# psg-dual-electronic-switching.net
KiCad netlist of a schematic drawn in EAGLE
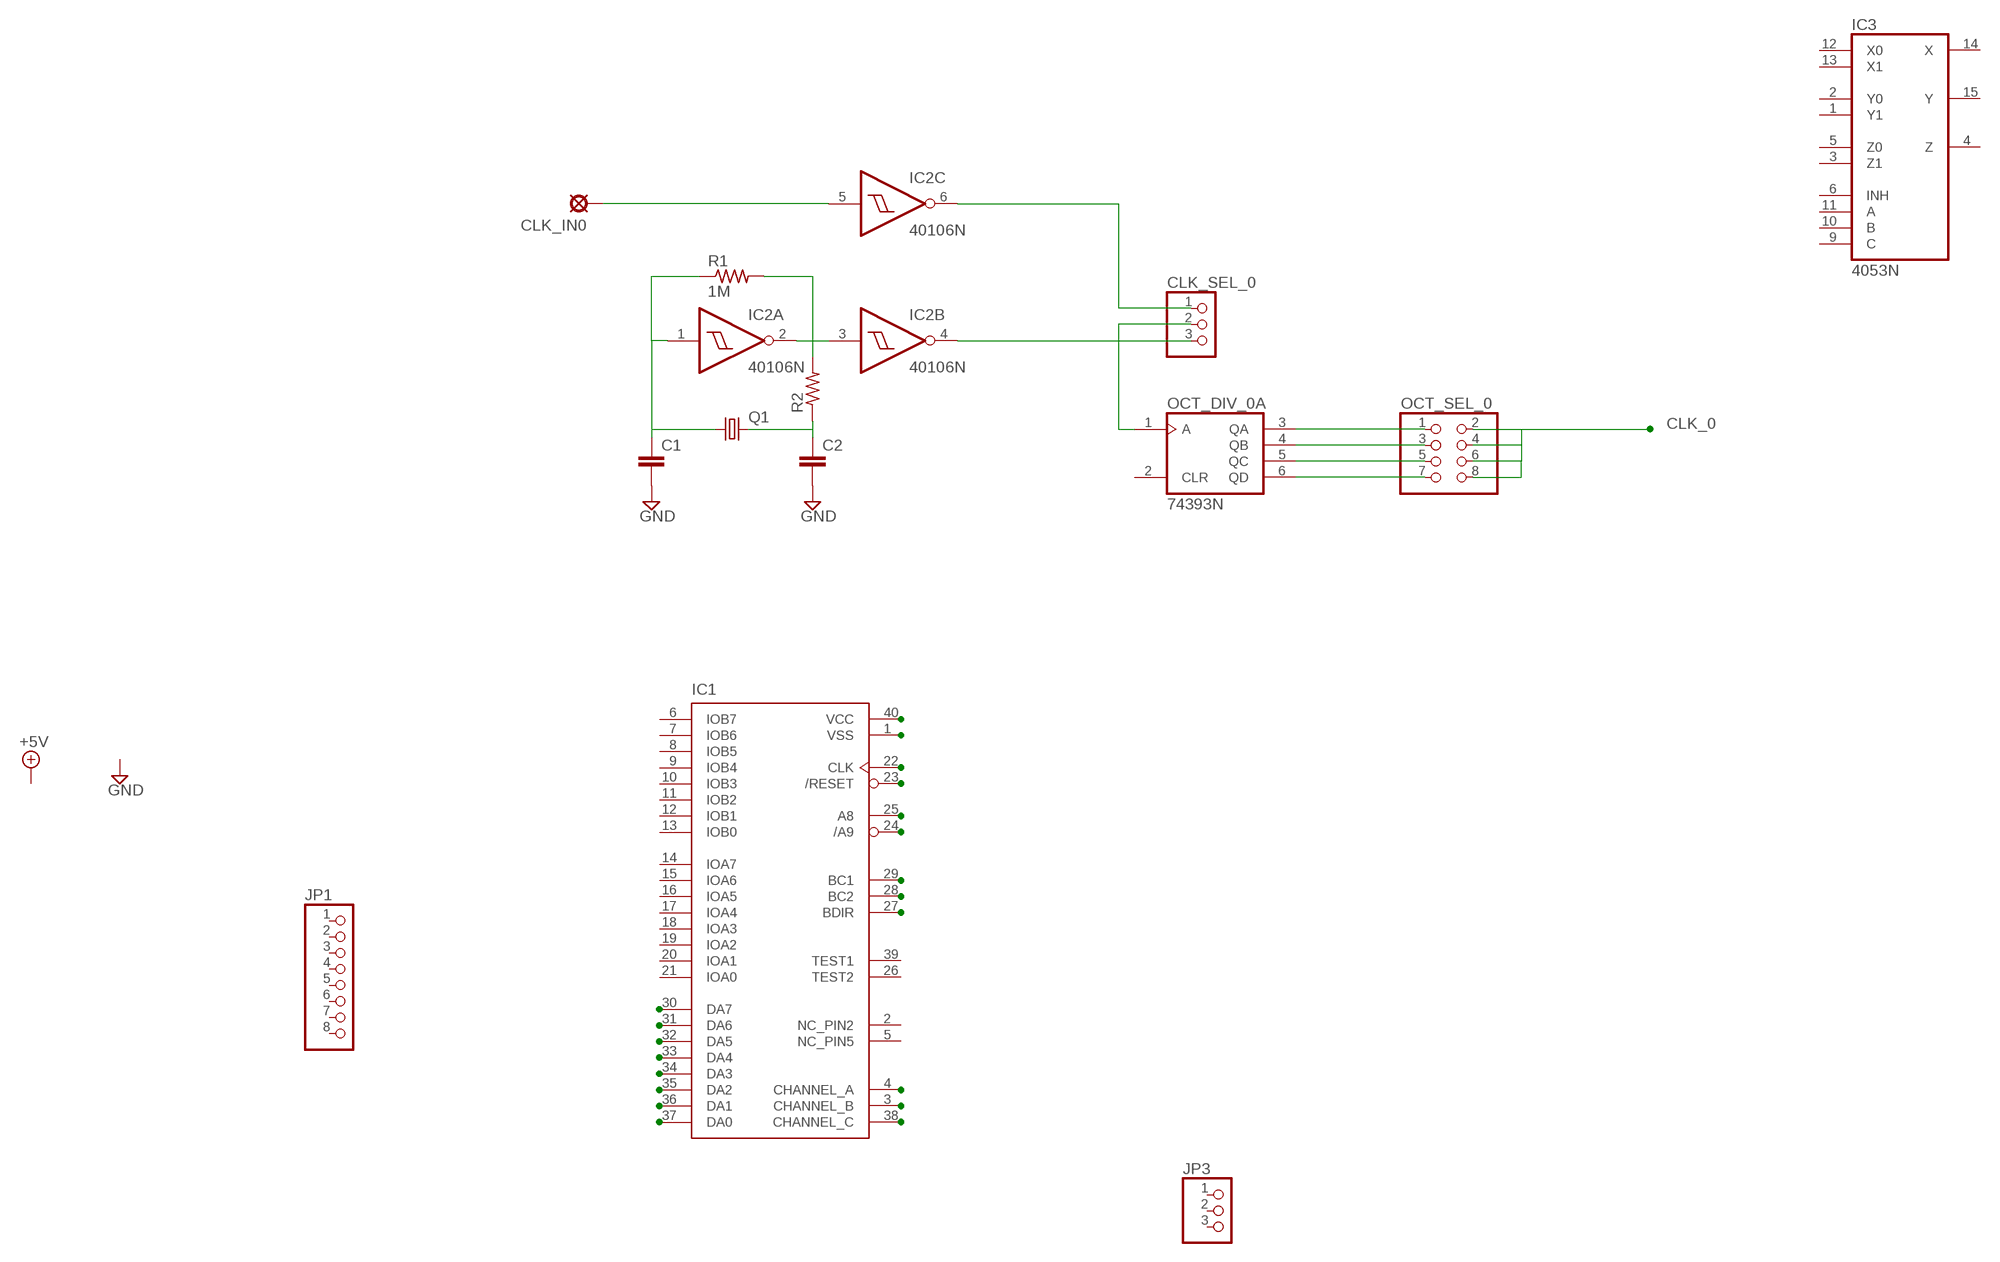
[diagram p0: schematic, sheet 1]

(export (version "E")
  (design (tool "Eeschema 10.0.6"))
  (components
    (comp (ref "C1")
      (value "050X030_0252")
      (footprint "eagle-import:050X030_025_2")
      (libsource (lib "eagle-import") (part "050X030_0252"))
    )
    (comp (ref "C2")
      (value "050X030_0252")
      (footprint "eagle-import:050X030_025_2")
      (libsource (lib "eagle-import") (part "050X030_0252"))
    )
    (comp (ref "CLK_IN0")
      (value "PAD")
      (footprint "eagle-import:SQUARE")
      (libsource (lib "eagle-import") (part "PAD"))
    )
    (comp (ref "CLK_SEL_0")
      (value "PINHD-1X3")
      (footprint "eagle-import:1X03")
      (libsource (lib "eagle-import") (part "PINHD-1X3"))
    )
    (comp (ref "IC1")
      (value "AY-3-8910")
      (footprint "eagle-import:DIL40")
      (libsource (lib "eagle-import") (part "AY-3-8910"))
    )
    (comp (ref "IC2")
      (value "40106N")
      (footprint "eagle-import:DIL14")
      (libsource (lib "eagle-import") (part "40106N"))
    )
    (comp (ref "IC3")
      (value "4053N")
      (footprint "eagle-import:DIL16")
      (libsource (lib "eagle-import") (part "4053N"))
    )
    (comp (ref "JP1")
      (value "PINHD-1X8")
      (footprint "eagle-import:1X08")
      (libsource (lib "eagle-import") (part "PINHD-1X8"))
    )
    (comp (ref "JP3")
      (value "PINHD-1X3")
      (footprint "eagle-import:1X03")
      (libsource (lib "eagle-import") (part "PINHD-1X3"))
    )
    (comp (ref "OCT_DIV_0")
      (value "74393N")
      (footprint "eagle-import:DIL14")
      (libsource (lib "eagle-import") (part "74393N"))
    )
    (comp (ref "OCT_SEL_0")
      (value "PINHD-2X4")
      (footprint "eagle-import:2X04")
      (libsource (lib "eagle-import") (part "PINHD-2X4"))
    )
    (comp (ref "Q1")
      (value "CRYSTALHC18U-V")
      (footprint "eagle-import:HC18U-V")
      (libsource (lib "eagle-import") (part "CRYSTALHC18U-V"))
    )
    (comp (ref "R1")
      (value "1M")
      (footprint "eagle-import:R0207_3")
      (libsource (lib "eagle-import") (part "6MM.3"))
    )
    (comp (ref "R2")
      (value "6MM.3")
      (footprint "eagle-import:R0207_3")
      (libsource (lib "eagle-import") (part "6MM.3"))
    )
  )
  (nets
    (net (code "2") (name "/CLK_0") (class "Default")
      (node (ref "OCT_SEL_0") (pin "2") (pinfunction "2_2") (pintype "passive"))
      (node (ref "OCT_SEL_0") (pin "4") (pinfunction "4_4") (pintype "passive"))
      (node (ref "OCT_SEL_0") (pin "6") (pinfunction "6_6") (pintype "passive"))
      (node (ref "OCT_SEL_0") (pin "8") (pinfunction "8_8") (pintype "passive"))
    )
    (net (code "3") (name "/VCC") (class "Default")
      (node (ref "IC1") (pin "40") (pinfunction "VCC_40") (pintype "power_in"))
    )
    (net (code "4") (name "/VSS") (class "Default")
      (node (ref "IC1") (pin "1") (pinfunction "VSS_1") (pintype "power_in"))
    )
    (net (code "5") (name "GND") (class "Default")
      (node (ref "C1") (pin "2") (pinfunction "2_2") (pintype "passive"))
      (node (ref "C2") (pin "2") (pinfunction "2_2") (pintype "passive"))
    )
    (net (code "6") (name "Net-(C2-Pad1)") (class "Default")
      (node (ref "C2") (pin "1") (pinfunction "1_1") (pintype "passive"))
      (node (ref "Q1") (pin "2") (pinfunction "2_2") (pintype "passive"))
      (node (ref "R2") (pin "1") (pinfunction "1_1") (pintype "passive"))
    )
    (net (code "7") (name "Net-(CLK_IN0-PAD)") (class "Default")
      (node (ref "CLK_IN0") (pin "1") (pinfunction "PAD_1") (pintype "passive"))
      (node (ref "IC2") (pin "5") (pinfunction "I_5") (pintype "input"))
    )
    (net (code "8") (name "Net-(IC2A-I)") (class "Default")
      (node (ref "C1") (pin "1") (pinfunction "1_1") (pintype "passive"))
      (node (ref "IC2") (pin "1") (pinfunction "I_1") (pintype "input"))
      (node (ref "Q1") (pin "1") (pinfunction "1_1") (pintype "passive"))
      (node (ref "R1") (pin "1") (pinfunction "1_1") (pintype "passive"))
    )
    (net (code "9") (name "Net-(IC2A-O)") (class "Default")
      (node (ref "IC2") (pin "2") (pinfunction "O_2") (pintype "output"))
      (node (ref "IC2") (pin "3") (pinfunction "I_3") (pintype "input"))
      (node (ref "R1") (pin "2") (pinfunction "2_2") (pintype "passive"))
      (node (ref "R2") (pin "2") (pinfunction "2_2") (pintype "passive"))
    )
    (net (code "10") (name "Net-(IC2B-O)") (class "Default")
      (node (ref "CLK_SEL_0") (pin "3") (pinfunction "3_3") (pintype "passive"))
      (node (ref "IC2") (pin "4") (pinfunction "O_4") (pintype "output"))
    )
    (net (code "11") (name "Net-(IC2C-O)") (class "Default")
      (node (ref "CLK_SEL_0") (pin "1") (pinfunction "1_1") (pintype "passive"))
      (node (ref "IC2") (pin "6") (pinfunction "O_6") (pintype "output"))
    )
    (net (code "12") (name "Net-(OCT_DIV_0A-A)") (class "Default")
      (node (ref "CLK_SEL_0") (pin "2") (pinfunction "2_2") (pintype "passive"))
      (node (ref "OCT_DIV_0") (pin "1") (pinfunction "A_1") (pintype "input"))
    )
    (net (code "13") (name "Net-(OCT_DIV_0A-QA)") (class "Default")
      (node (ref "OCT_DIV_0") (pin "3") (pinfunction "QA_3") (pintype "output"))
      (node (ref "OCT_SEL_0") (pin "1") (pinfunction "1_1") (pintype "passive"))
    )
    (net (code "14") (name "Net-(OCT_DIV_0A-QB)") (class "Default")
      (node (ref "OCT_DIV_0") (pin "4") (pinfunction "QB_4") (pintype "output"))
      (node (ref "OCT_SEL_0") (pin "3") (pinfunction "3_3") (pintype "passive"))
    )
    (net (code "15") (name "Net-(OCT_DIV_0A-QC)") (class "Default")
      (node (ref "OCT_DIV_0") (pin "5") (pinfunction "QC_5") (pintype "output"))
      (node (ref "OCT_SEL_0") (pin "5") (pinfunction "5_5") (pintype "passive"))
    )
    (net (code "16") (name "Net-(OCT_DIV_0A-QD)") (class "Default")
      (node (ref "OCT_DIV_0") (pin "6") (pinfunction "QD_6") (pintype "output"))
      (node (ref "OCT_SEL_0") (pin "7") (pinfunction "7_7") (pintype "passive"))
    )
    (net (code "17") (name "unconnected-(IC1-A8-Pad25)") (class "Default")
      (node (ref "IC1") (pin "25") (pinfunction "A8_25") (pintype "bidirectional"))
    )
    (net (code "18") (name "unconnected-(IC1-BC1-Pad29)") (class "Default")
      (node (ref "IC1") (pin "29") (pinfunction "BC1_29") (pintype "input"))
    )
    (net (code "19") (name "unconnected-(IC1-BC2-Pad28)") (class "Default")
      (node (ref "IC1") (pin "28") (pinfunction "BC2_28") (pintype "input"))
    )
    (net (code "20") (name "unconnected-(IC1-BDIR-Pad27)") (class "Default")
      (node (ref "IC1") (pin "27") (pinfunction "BDIR_27") (pintype "input"))
    )
    (net (code "21") (name "unconnected-(IC1-CHANNEL_A-Pad4)") (class "Default")
      (node (ref "IC1") (pin "4") (pinfunction "CHANNEL_A_4") (pintype "output"))
    )
    (net (code "22") (name "unconnected-(IC1-CHANNEL_B-Pad3)") (class "Default")
      (node (ref "IC1") (pin "3") (pinfunction "CHANNEL_B_3") (pintype "output"))
    )
    (net (code "23") (name "unconnected-(IC1-CHANNEL_C-Pad38)") (class "Default")
      (node (ref "IC1") (pin "38") (pinfunction "CHANNEL_C_38") (pintype "output"))
    )
    (net (code "24") (name "unconnected-(IC1-CLK-Pad22)") (class "Default")
      (node (ref "IC1") (pin "22") (pinfunction "CLK_22") (pintype "input"))
    )
    (net (code "25") (name "unconnected-(IC1-DA0-Pad37)") (class "Default")
      (node (ref "IC1") (pin "37") (pinfunction "DA0_37") (pintype "bidirectional"))
    )
    (net (code "26") (name "unconnected-(IC1-DA1-Pad36)") (class "Default")
      (node (ref "IC1") (pin "36") (pinfunction "DA1_36") (pintype "bidirectional"))
    )
    (net (code "27") (name "unconnected-(IC1-DA2-Pad35)") (class "Default")
      (node (ref "IC1") (pin "35") (pinfunction "DA2_35") (pintype "bidirectional"))
    )
    (net (code "28") (name "unconnected-(IC1-DA3-Pad34)") (class "Default")
      (node (ref "IC1") (pin "34") (pinfunction "DA3_34") (pintype "bidirectional"))
    )
    (net (code "29") (name "unconnected-(IC1-DA4-Pad33)") (class "Default")
      (node (ref "IC1") (pin "33") (pinfunction "DA4_33") (pintype "bidirectional"))
    )
    (net (code "30") (name "unconnected-(IC1-DA5-Pad32)") (class "Default")
      (node (ref "IC1") (pin "32") (pinfunction "DA5_32") (pintype "bidirectional"))
    )
    (net (code "31") (name "unconnected-(IC1-DA6-Pad31)") (class "Default")
      (node (ref "IC1") (pin "31") (pinfunction "DA6_31") (pintype "bidirectional"))
    )
    (net (code "32") (name "unconnected-(IC1-DA7-Pad30)") (class "Default")
      (node (ref "IC1") (pin "30") (pinfunction "DA7_30") (pintype "bidirectional"))
    )
    (net (code "33") (name "unconnected-(IC1-IOA0-Pad21)") (class "Default")
      (node (ref "IC1") (pin "21") (pinfunction "IOA0_21") (pintype "bidirectional"))
    )
    (net (code "34") (name "unconnected-(IC1-IOA1-Pad20)") (class "Default")
      (node (ref "IC1") (pin "20") (pinfunction "IOA1_20") (pintype "bidirectional"))
    )
    (net (code "35") (name "unconnected-(IC1-IOA2-Pad19)") (class "Default")
      (node (ref "IC1") (pin "19") (pinfunction "IOA2_19") (pintype "bidirectional"))
    )
    (net (code "36") (name "unconnected-(IC1-IOA3-Pad18)") (class "Default")
      (node (ref "IC1") (pin "18") (pinfunction "IOA3_18") (pintype "bidirectional"))
    )
    (net (code "37") (name "unconnected-(IC1-IOA4-Pad17)") (class "Default")
      (node (ref "IC1") (pin "17") (pinfunction "IOA4_17") (pintype "bidirectional"))
    )
    (net (code "38") (name "unconnected-(IC1-IOA5-Pad16)") (class "Default")
      (node (ref "IC1") (pin "16") (pinfunction "IOA5_16") (pintype "bidirectional"))
    )
    (net (code "39") (name "unconnected-(IC1-IOA6-Pad15)") (class "Default")
      (node (ref "IC1") (pin "15") (pinfunction "IOA6_15") (pintype "bidirectional"))
    )
    (net (code "40") (name "unconnected-(IC1-IOA7-Pad14)") (class "Default")
      (node (ref "IC1") (pin "14") (pinfunction "IOA7_14") (pintype "bidirectional"))
    )
    (net (code "41") (name "unconnected-(IC1-IOB0-Pad13)") (class "Default")
      (node (ref "IC1") (pin "13") (pinfunction "IOB0_13") (pintype "bidirectional"))
    )
    (net (code "42") (name "unconnected-(IC1-IOB1-Pad12)") (class "Default")
      (node (ref "IC1") (pin "12") (pinfunction "IOB1_12") (pintype "bidirectional"))
    )
    (net (code "43") (name "unconnected-(IC1-IOB2-Pad11)") (class "Default")
      (node (ref "IC1") (pin "11") (pinfunction "IOB2_11") (pintype "bidirectional"))
    )
    (net (code "44") (name "unconnected-(IC1-IOB3-Pad10)") (class "Default")
      (node (ref "IC1") (pin "10") (pinfunction "IOB3_10") (pintype "bidirectional"))
    )
    (net (code "45") (name "unconnected-(IC1-IOB4-Pad9)") (class "Default")
      (node (ref "IC1") (pin "9") (pinfunction "IOB4_9") (pintype "bidirectional"))
    )
    (net (code "46") (name "unconnected-(IC1-IOB5-Pad8)") (class "Default")
      (node (ref "IC1") (pin "8") (pinfunction "IOB5_8") (pintype "bidirectional"))
    )
    (net (code "47") (name "unconnected-(IC1-IOB6-Pad7)") (class "Default")
      (node (ref "IC1") (pin "7") (pinfunction "IOB6_7") (pintype "bidirectional"))
    )
    (net (code "48") (name "unconnected-(IC1-IOB7-Pad6)") (class "Default")
      (node (ref "IC1") (pin "6") (pinfunction "IOB7_6") (pintype "bidirectional"))
    )
    (net (code "49") (name "unconnected-(IC1-NC_PIN2-Pad2)") (class "Default")
      (node (ref "IC1") (pin "2") (pinfunction "NC_PIN2_2") (pintype "no_connect"))
    )
    (net (code "50") (name "unconnected-(IC1-NC_PIN5-Pad5)") (class "Default")
      (node (ref "IC1") (pin "5") (pinfunction "NC_PIN5_5") (pintype "bidirectional"))
    )
    (net (code "51") (name "unconnected-(IC1-TEST1-Pad39)") (class "Default")
      (node (ref "IC1") (pin "39") (pinfunction "TEST1_39") (pintype "no_connect"))
    )
    (net (code "52") (name "unconnected-(IC1-TEST2-Pad26)") (class "Default")
      (node (ref "IC1") (pin "26") (pinfunction "TEST2_26") (pintype "no_connect"))
    )
    (net (code "53") (name "unconnected-(IC1-{slash}A9-Pad24)") (class "Default")
      (node (ref "IC1") (pin "24") (pinfunction "/A9_24") (pintype "bidirectional"))
    )
    (net (code "54") (name "unconnected-(IC1-{slash}RESET-Pad23)") (class "Default")
      (node (ref "IC1") (pin "23") (pinfunction "/RESET_23") (pintype "input"))
    )
    (net (code "55") (name "unconnected-(IC3A-A-Pad11)") (class "Default")
      (node (ref "IC3") (pin "11") (pinfunction "A_11") (pintype "input"))
    )
    (net (code "56") (name "unconnected-(IC3A-B-Pad10)") (class "Default")
      (node (ref "IC3") (pin "10") (pinfunction "B_10") (pintype "input"))
    )
    (net (code "57") (name "unconnected-(IC3A-C-Pad9)") (class "Default")
      (node (ref "IC3") (pin "9") (pinfunction "C_9") (pintype "input"))
    )
    (net (code "58") (name "unconnected-(IC3A-INH-Pad6)") (class "Default")
      (node (ref "IC3") (pin "6") (pinfunction "INH_6") (pintype "input"))
    )
    (net (code "59") (name "unconnected-(IC3A-X-Pad14)") (class "Default")
      (node (ref "IC3") (pin "14") (pinfunction "X_14") (pintype "bidirectional"))
    )
    (net (code "60") (name "unconnected-(IC3A-X0-Pad12)") (class "Default")
      (node (ref "IC3") (pin "12") (pinfunction "X0_12") (pintype "bidirectional"))
    )
    (net (code "61") (name "unconnected-(IC3A-X1-Pad13)") (class "Default")
      (node (ref "IC3") (pin "13") (pinfunction "X1_13") (pintype "bidirectional"))
    )
    (net (code "62") (name "unconnected-(IC3A-Y-Pad15)") (class "Default")
      (node (ref "IC3") (pin "15") (pinfunction "Y_15") (pintype "bidirectional"))
    )
    (net (code "63") (name "unconnected-(IC3A-Y0-Pad2)") (class "Default")
      (node (ref "IC3") (pin "2") (pinfunction "Y0_2") (pintype "bidirectional"))
    )
    (net (code "64") (name "unconnected-(IC3A-Y1-Pad1)") (class "Default")
      (node (ref "IC3") (pin "1") (pinfunction "Y1_1") (pintype "bidirectional"))
    )
    (net (code "65") (name "unconnected-(IC3A-Z-Pad4)") (class "Default")
      (node (ref "IC3") (pin "4") (pinfunction "Z_4") (pintype "bidirectional"))
    )
    (net (code "66") (name "unconnected-(IC3A-Z0-Pad5)") (class "Default")
      (node (ref "IC3") (pin "5") (pinfunction "Z0_5") (pintype "bidirectional"))
    )
    (net (code "67") (name "unconnected-(IC3A-Z1-Pad3)") (class "Default")
      (node (ref "IC3") (pin "3") (pinfunction "Z1_3") (pintype "bidirectional"))
    )
    (net (code "68") (name "unconnected-(JP1-Pad1)") (class "Default")
      (node (ref "JP1") (pin "1") (pinfunction "1_1") (pintype "passive"))
    )
    (net (code "69") (name "unconnected-(JP1-Pad2)") (class "Default")
      (node (ref "JP1") (pin "2") (pinfunction "2_2") (pintype "passive"))
    )
    (net (code "70") (name "unconnected-(JP1-Pad3)") (class "Default")
      (node (ref "JP1") (pin "3") (pinfunction "3_3") (pintype "passive"))
    )
    (net (code "71") (name "unconnected-(JP1-Pad4)") (class "Default")
      (node (ref "JP1") (pin "4") (pinfunction "4_4") (pintype "passive"))
    )
    (net (code "72") (name "unconnected-(JP1-Pad5)") (class "Default")
      (node (ref "JP1") (pin "5") (pinfunction "5_5") (pintype "passive"))
    )
    (net (code "73") (name "unconnected-(JP1-Pad6)") (class "Default")
      (node (ref "JP1") (pin "6") (pinfunction "6_6") (pintype "passive"))
    )
    (net (code "74") (name "unconnected-(JP1-Pad7)") (class "Default")
      (node (ref "JP1") (pin "7") (pinfunction "7_7") (pintype "passive"))
    )
    (net (code "75") (name "unconnected-(JP1-Pad8)") (class "Default")
      (node (ref "JP1") (pin "8") (pinfunction "8_8") (pintype "passive"))
    )
    (net (code "76") (name "unconnected-(JP3-Pad1)") (class "Default")
      (node (ref "JP3") (pin "1") (pinfunction "1_1") (pintype "passive"))
    )
    (net (code "77") (name "unconnected-(JP3-Pad2)") (class "Default")
      (node (ref "JP3") (pin "2") (pinfunction "2_2") (pintype "passive"))
    )
    (net (code "78") (name "unconnected-(JP3-Pad3)") (class "Default")
      (node (ref "JP3") (pin "3") (pinfunction "3_3") (pintype "passive"))
    )
    (net (code "79") (name "unconnected-(OCT_DIV_0A-CLR-Pad2)") (class "Default")
      (node (ref "OCT_DIV_0") (pin "2") (pinfunction "CLR_2") (pintype "input"))
    )
  )
)
